# Pit_Crew.net
KiCad netlist of a schematic drawn in EAGLE
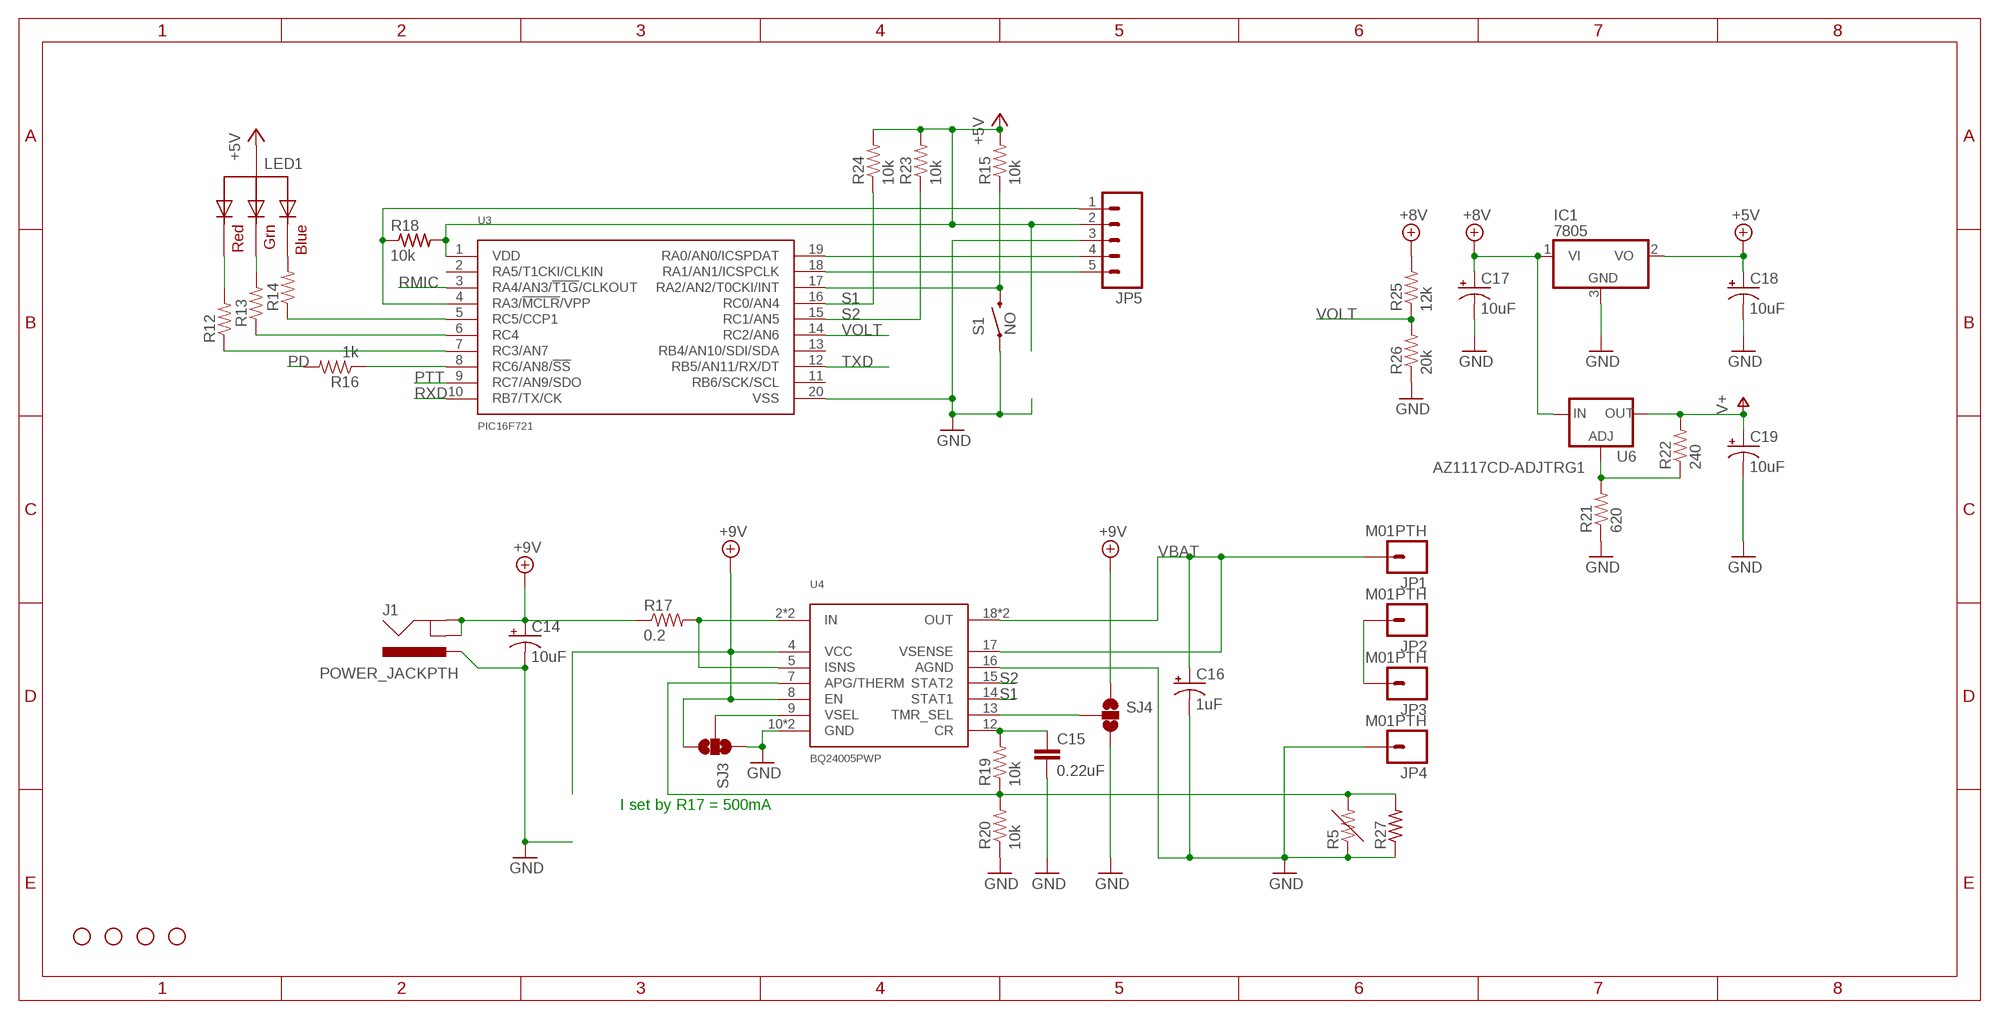
[diagram p0: schematic, sheet 1]
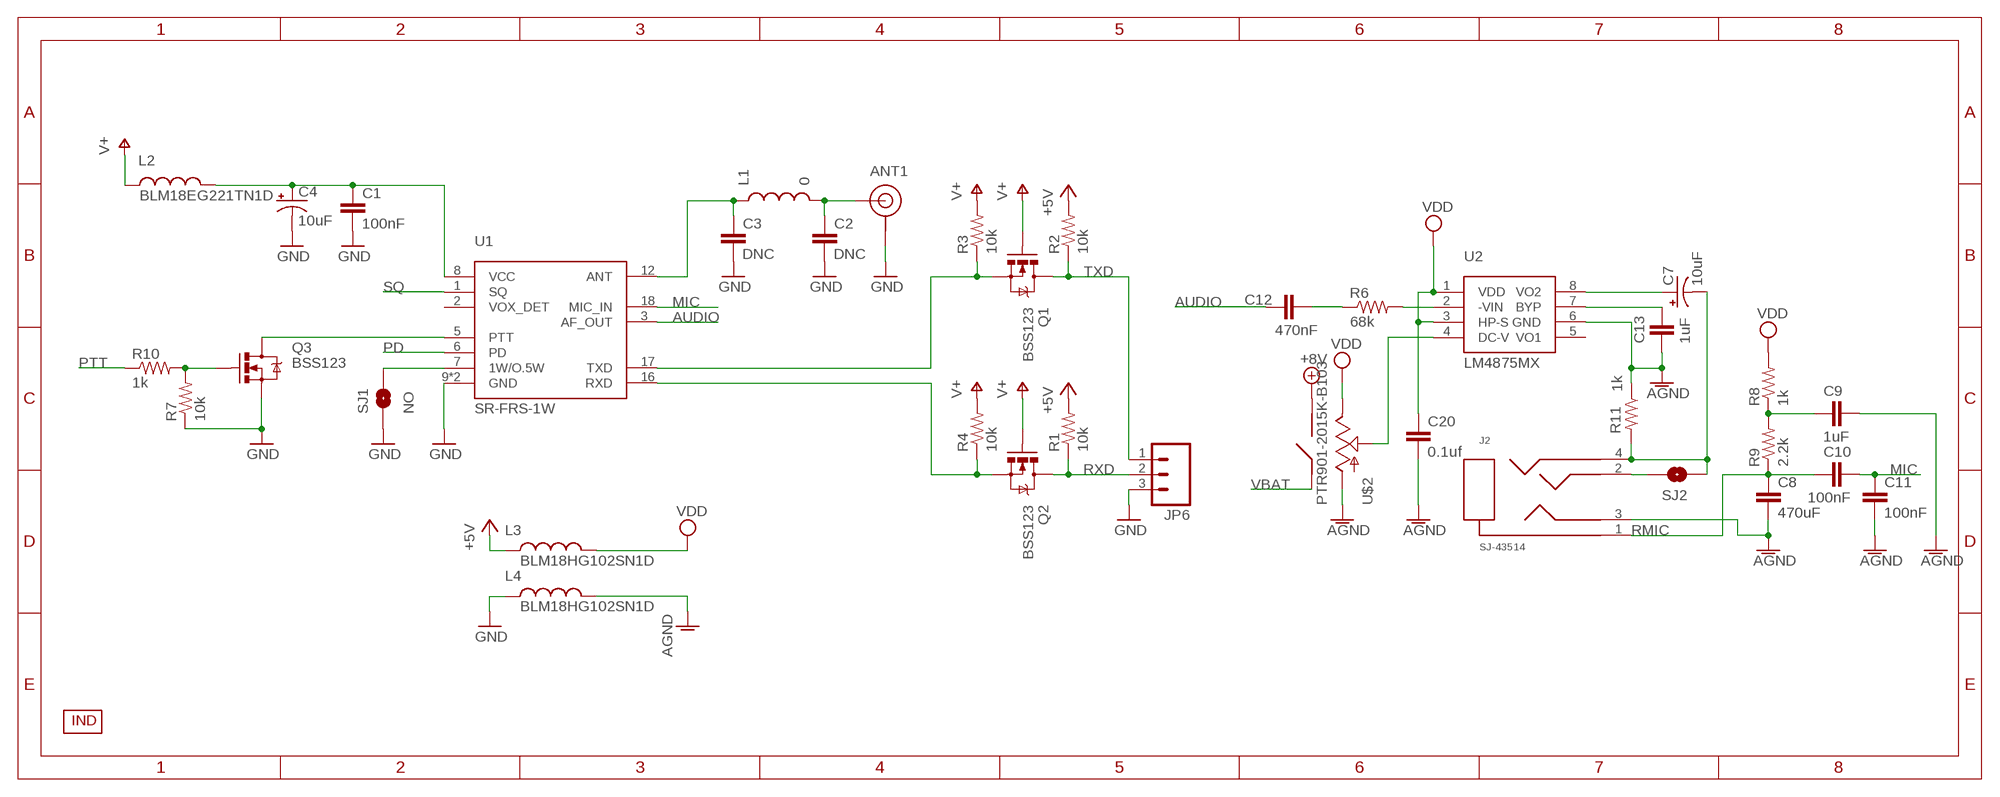
[diagram p1: schematic, sheet 2]

(export (version "E")
  (design (tool "Eeschema 10.0.6"))
  (components
    (comp (ref "ANT1")
      (value "SMA")
      (footprint "eagle-import:CONSMA002")
      (libsource (lib "eagle-import") (part "SMA"))
    )
    (comp (ref "C1")
      (value "100nF")
      (footprint "eagle-import:0805")
      (libsource (lib "eagle-import") (part "CAP0805"))
    )
    (comp (ref "C2")
      (value "DNC")
      (footprint "eagle-import:0805")
      (libsource (lib "eagle-import") (part "CAP0805"))
    )
    (comp (ref "C3")
      (value "DNC")
      (footprint "eagle-import:0805")
      (libsource (lib "eagle-import") (part "CAP0805"))
    )
    (comp (ref "C4")
      (value "10uF")
      (footprint "eagle-import:EIA3216")
      (libsource (lib "eagle-import") (part "CAP_POL1206"))
    )
    (comp (ref "C7")
      (value "10uF")
      (footprint "eagle-import:EIA3216")
      (libsource (lib "eagle-import") (part "10UF-TANT"))
    )
    (comp (ref "C8")
      (value "470uF")
      (footprint "eagle-import:0805")
      (libsource (lib "eagle-import") (part "CAP0805"))
    )
    (comp (ref "C9")
      (value "1uF")
      (footprint "eagle-import:0805")
      (libsource (lib "eagle-import") (part "CAP0805"))
    )
    (comp (ref "C10")
      (value "100nF")
      (footprint "eagle-import:0805")
      (libsource (lib "eagle-import") (part "CAP0805"))
    )
    (comp (ref "C11")
      (value "100nF")
      (footprint "eagle-import:0805")
      (libsource (lib "eagle-import") (part "CAP0805"))
    )
    (comp (ref "C12")
      (value "470nF")
      (footprint "eagle-import:0805")
      (libsource (lib "eagle-import") (part "CAP0805"))
    )
    (comp (ref "C13")
      (value "1uF")
      (footprint "eagle-import:0805")
      (libsource (lib "eagle-import") (part "CAP0805"))
    )
    (comp (ref "C20")
      (value "0.1uf")
      (footprint "eagle-import:0805")
      (libsource (lib "eagle-import") (part "CAP0805"))
    )
    (comp (ref "J2")
      (value "SJ-43514")
      (footprint "eagle-import:SJ-43514")
      (libsource (lib "eagle-import") (part "SJ-43514"))
    )
    (comp (ref "JP6")
      (value "M03LOCK")
      (footprint "eagle-import:1X03_LOCK")
      (libsource (lib "eagle-import") (part "M03LOCK"))
    )
    (comp (ref "L1")
      (value "0")
      (footprint "eagle-import:1007")
      (libsource (lib "eagle-import") (part "INDUCTOR1007"))
    )
    (comp (ref "L2")
      (value "BLM18EG221TN1D")
      (footprint "eagle-import:0603")
      (libsource (lib "eagle-import") (part "INDUCTOR0603"))
    )
    (comp (ref "L3")
      (value "BLM18HG102SN1D")
      (footprint "eagle-import:0603")
      (libsource (lib "eagle-import") (part "INDUCTOR0603"))
    )
    (comp (ref "L4")
      (value "BLM18HG102SN1D")
      (footprint "eagle-import:0603")
      (libsource (lib "eagle-import") (part "INDUCTOR0603"))
    )
    (comp (ref "Q1")
      (value "BSS123")
      (footprint "eagle-import:SOT23")
      (libsource (lib "eagle-import") (part "MOSFET-NCHANNELBSS123LT1G"))
    )
    (comp (ref "Q2")
      (value "BSS123")
      (footprint "eagle-import:SOT23")
      (libsource (lib "eagle-import") (part "MOSFET-NCHANNELBSS123LT1G"))
    )
    (comp (ref "Q3")
      (value "BSS123")
      (footprint "eagle-import:SOT23")
      (libsource (lib "eagle-import") (part "MOSFET-NCHANNELBSS123LT1G"))
    )
    (comp (ref "R1")
      (value "10k")
      (footprint "eagle-import:0805")
      (libsource (lib "eagle-import") (part "RESISTOR0805-RES"))
    )
    (comp (ref "R2")
      (value "10k")
      (footprint "eagle-import:0805")
      (libsource (lib "eagle-import") (part "RESISTOR0805-RES"))
    )
    (comp (ref "R3")
      (value "10k")
      (footprint "eagle-import:0805")
      (libsource (lib "eagle-import") (part "RESISTOR0805-RES"))
    )
    (comp (ref "R4")
      (value "10k")
      (footprint "eagle-import:0805")
      (libsource (lib "eagle-import") (part "RESISTOR0805-RES"))
    )
    (comp (ref "R6")
      (value "68k")
      (footprint "eagle-import:0805")
      (libsource (lib "eagle-import") (part "RESISTOR0805-RES"))
    )
    (comp (ref "R7")
      (value "10k")
      (footprint "eagle-import:0805")
      (libsource (lib "eagle-import") (part "RESISTOR0805-RES"))
    )
    (comp (ref "R8")
      (value "1k")
      (footprint "eagle-import:0805")
      (libsource (lib "eagle-import") (part "RESISTOR0805-RES"))
    )
    (comp (ref "R9")
      (value "2.2k")
      (footprint "eagle-import:0805")
      (libsource (lib "eagle-import") (part "RESISTOR0805-RES"))
    )
    (comp (ref "R10")
      (value "1k")
      (footprint "eagle-import:0805")
      (libsource (lib "eagle-import") (part "RESISTOR0805-RES"))
    )
    (comp (ref "R11")
      (value "1k")
      (footprint "eagle-import:0805")
      (libsource (lib "eagle-import") (part "RESISTOR0805-RES"))
    )
    (comp (ref "SJ1")
      (value "NO")
      (footprint "eagle-import:SJ_2S-NO")
      (libsource (lib "eagle-import") (part "SOLDERJUMPERNO"))
    )
    (comp (ref "SJ2")
      (value "SOLDERJUMPERNO")
      (footprint "eagle-import:SJ_2S-NO")
      (libsource (lib "eagle-import") (part "SOLDERJUMPERNO"))
    )
    (comp (ref "U$2")
      (value "PTR901-2015K-B103")
      (footprint "eagle-import:PTR901-2015K-B103")
      (libsource (lib "eagle-import") (part "PTR901-2015K-B103"))
    )
    (comp (ref "U$3")
      (value "INDPK1")
      (footprint "eagle-import:PICKIT-PIN-1")
      (libsource (lib "eagle-import") (part "INDPK1"))
    )
    (comp (ref "U1")
      (value "SR-FRS-1W")
      (footprint "eagle-import:SR-FRS-1W")
      (libsource (lib "eagle-import") (part "SR-FRS-1W"))
    )
    (comp (ref "U2")
      (value "LM4875MX")
      (footprint "eagle-import:SO-8")
      (libsource (lib "eagle-import") (part "LM4875MX"))
    )
    (comp (ref "C14")
      (value "10uF")
      (footprint "eagle-import:EIA3216")
      (libsource (lib "eagle-import") (part "10UF-TANT"))
    )
    (comp (ref "C15")
      (value "0.22uF")
      (footprint "eagle-import:0805")
      (libsource (lib "eagle-import") (part "CAP0805"))
    )
    (comp (ref "C16")
      (value "1uF")
      (footprint "eagle-import:EIA3216")
      (libsource (lib "eagle-import") (part "10UF-TANT"))
    )
    (comp (ref "C17")
      (value "10uF")
      (footprint "eagle-import:EIA3216")
      (libsource (lib "eagle-import") (part "10UF-TANT"))
    )
    (comp (ref "C18")
      (value "10uF")
      (footprint "eagle-import:EIA3216")
      (libsource (lib "eagle-import") (part "10UF-TANT"))
    )
    (comp (ref "C19")
      (value "10uF")
      (footprint "eagle-import:EIA3216")
      (libsource (lib "eagle-import") (part "10UF-TANT"))
    )
    (comp (ref "IC1")
      (value "7805")
      (footprint "eagle-import:TO252")
      (libsource (lib "eagle-import") (part "78DT06"))
    )
    (comp (ref "J1")
      (value "POWER_JACKPTH")
      (footprint "eagle-import:POWER_JACK_PTH")
      (libsource (lib "eagle-import") (part "POWER_JACKPTH"))
    )
    (comp (ref "JP1")
      (value "M01PTH")
      (footprint "eagle-import:1X01")
      (libsource (lib "eagle-import") (part "M01PTH"))
    )
    (comp (ref "JP2")
      (value "M01PTH")
      (footprint "eagle-import:1X01")
      (libsource (lib "eagle-import") (part "M01PTH"))
    )
    (comp (ref "JP3")
      (value "M01PTH")
      (footprint "eagle-import:1X01")
      (libsource (lib "eagle-import") (part "M01PTH"))
    )
    (comp (ref "JP4")
      (value "M01PTH")
      (footprint "eagle-import:1X01")
      (libsource (lib "eagle-import") (part "M01PTH"))
    )
    (comp (ref "JP5")
      (value "M05LOCK_LONGPADS")
      (footprint "eagle-import:1X05_LOCK_LONGPADS")
      (libsource (lib "eagle-import") (part "M05LOCK_LONGPADS"))
    )
    (comp (ref "LED1")
      (value "RGBLED_CA-5MM")
      (footprint "eagle-import:LED5MMRGB")
      (libsource (lib "eagle-import") (part "RGBLED_CA-5MM"))
    )
    (comp (ref "R5")
      (value "RESISTOR0805-RES")
      (footprint "eagle-import:0805")
      (libsource (lib "eagle-import") (part "RESISTOR0805-RES"))
    )
    (comp (ref "R12")
      (value "RESISTOR0805-RES")
      (footprint "eagle-import:0805")
      (libsource (lib "eagle-import") (part "RESISTOR0805-RES"))
    )
    (comp (ref "R13")
      (value "RESISTOR0805-RES")
      (footprint "eagle-import:0805")
      (libsource (lib "eagle-import") (part "RESISTOR0805-RES"))
    )
    (comp (ref "R14")
      (value "RESISTOR0805-RES")
      (footprint "eagle-import:0805")
      (libsource (lib "eagle-import") (part "RESISTOR0805-RES"))
    )
    (comp (ref "R15")
      (value "10k")
      (footprint "eagle-import:0805")
      (libsource (lib "eagle-import") (part "RESISTOR0805-RES"))
    )
    (comp (ref "R16")
      (value "1k")
      (footprint "eagle-import:0805")
      (libsource (lib "eagle-import") (part "RESISTOR0805-RES"))
    )
    (comp (ref "R17")
      (value "0.2")
      (footprint "eagle-import:R2512")
      (libsource (lib "eagle-import") (part "RESISTOR2512"))
    )
    (comp (ref "R18")
      (value "10k")
      (footprint "eagle-import:R0805")
      (libsource (lib "eagle-import") (part "R-US_R0805"))
    )
    (comp (ref "R19")
      (value "10k")
      (footprint "eagle-import:0805")
      (libsource (lib "eagle-import") (part "RESISTOR0805-RES"))
    )
    (comp (ref "R20")
      (value "10k")
      (footprint "eagle-import:0805")
      (libsource (lib "eagle-import") (part "RESISTOR0805-RES"))
    )
    (comp (ref "R21")
      (value "620")
      (footprint "eagle-import:0805")
      (libsource (lib "eagle-import") (part "RESISTOR0805-RES"))
    )
    (comp (ref "R22")
      (value "240")
      (footprint "eagle-import:0805")
      (libsource (lib "eagle-import") (part "RESISTOR0805-RES"))
    )
    (comp (ref "R23")
      (value "10k")
      (footprint "eagle-import:0805")
      (libsource (lib "eagle-import") (part "RESISTOR0805-RES"))
    )
    (comp (ref "R24")
      (value "10k")
      (footprint "eagle-import:0805")
      (libsource (lib "eagle-import") (part "RESISTOR0805-RES"))
    )
    (comp (ref "R25")
      (value "12k")
      (footprint "eagle-import:0805")
      (libsource (lib "eagle-import") (part "RESISTOR0805-RES"))
    )
    (comp (ref "R26")
      (value "20k")
      (footprint "eagle-import:0805")
      (libsource (lib "eagle-import") (part "RESISTOR0805-RES"))
    )
    (comp (ref "R27")
      (value "R-US_0207/7")
      (footprint "eagle-import:0207_7")
      (libsource (lib "eagle-import") (part "R-US_0207/7"))
    )
    (comp (ref "S1")
      (value "NO")
      (footprint "eagle-import:TACTILE-PTH-SIDEEZ")
      (libsource (lib "eagle-import") (part "SWITCH-MOMENTARY-2SIDE_EZ"))
    )
    (comp (ref "SJ3")
      (value "SOLDERJUMPER_2WAYS")
      (footprint "eagle-import:SJ_3")
      (libsource (lib "eagle-import") (part "SOLDERJUMPER_2WAYS"))
    )
    (comp (ref "SJ4")
      (value "SOLDERJUMPER_2WAYS")
      (footprint "eagle-import:SJ_3")
      (libsource (lib "eagle-import") (part "SOLDERJUMPER_2WAYS"))
    )
    (comp (ref "STANDOFF1")
      (value "STAND-OFF")
      (footprint "eagle-import:STAND-OFF")
      (libsource (lib "eagle-import") (part "STAND-OFF"))
    )
    (comp (ref "STANDOFF2")
      (value "STAND-OFF")
      (footprint "eagle-import:STAND-OFF")
      (libsource (lib "eagle-import") (part "STAND-OFF"))
    )
    (comp (ref "STANDOFF3")
      (value "STAND-OFF")
      (footprint "eagle-import:STAND-OFF")
      (libsource (lib "eagle-import") (part "STAND-OFF"))
    )
    (comp (ref "STANDOFF4")
      (value "STAND-OFF")
      (footprint "eagle-import:STAND-OFF")
      (libsource (lib "eagle-import") (part "STAND-OFF"))
    )
    (comp (ref "U3")
      (value "PIC16F721")
      (footprint "eagle-import:SSOP-20")
      (libsource (lib "eagle-import") (part "PIC16F721"))
    )
    (comp (ref "U4")
      (value "BQ24005PWP")
      (footprint "eagle-import:HTSSOP-20")
      (libsource (lib "eagle-import") (part "BQ24005PWP"))
    )
    (comp (ref "U6")
      (value "AZ1117CD-ADJTRG1")
      (footprint "eagle-import:V-REG_DPACK")
      (libsource (lib "eagle-import") (part "V_REG_317DPACK"))
    )
  )
  (nets
    (net (code "1") (name "+5V") (class "Default")
      (node (ref "C18") (pin "A") (pinfunction "+_A") (pintype "passive"))
      (node (ref "IC1") (pin "2") (pinfunction "VO_2") (pintype "passive"))
      (node (ref "JP5") (pin "2") (pinfunction "2_2") (pintype "passive"))
      (node (ref "L3") (pin "1") (pinfunction "1_1") (pintype "passive"))
      (node (ref "LED1") (pin "2") (pinfunction "VCC_2") (pintype "bidirectional"))
      (node (ref "R1") (pin "2") (pinfunction "2_2") (pintype "passive"))
      (node (ref "R15") (pin "2") (pinfunction "2_2") (pintype "passive"))
      (node (ref "R18") (pin "2") (pinfunction "2_2") (pintype "passive"))
      (node (ref "R2") (pin "2") (pinfunction "2_2") (pintype "passive"))
      (node (ref "R23") (pin "2") (pinfunction "2_2") (pintype "passive"))
      (node (ref "R24") (pin "2") (pinfunction "2_2") (pintype "passive"))
      (node (ref "U3") (pin "1") (pinfunction "VDD_1") (pintype "bidirectional"))
    )
    (net (code "2") (name "+8V") (class "Default")
      (node (ref "C17") (pin "A") (pinfunction "+_A") (pintype "passive"))
      (node (ref "IC1") (pin "1") (pinfunction "VI_1") (pintype "input"))
      (node (ref "R25") (pin "2") (pinfunction "2_2") (pintype "passive"))
      (node (ref "U$2") (pin "S1") (pinfunction "S1_S1") (pintype "passive"))
      (node (ref "U6") (pin "3") (pinfunction "IN_3") (pintype "input"))
    )
    (net (code "3") (name "+9V") (class "Default")
      (node (ref "C14") (pin "A") (pinfunction "+_A") (pintype "passive"))
      (node (ref "J1") (pin "GND") (pinfunction "GND_GND") (pintype "bidirectional"))
      (node (ref "J1") (pin "GNDBREAK") (pinfunction "GNDBREAK_GNDBREAK") (pintype "bidirectional"))
      (node (ref "R17") (pin "1") (pinfunction "1_1") (pintype "passive"))
      (node (ref "SJ3") (pin "3") (pinfunction "3_3") (pintype "passive"))
      (node (ref "SJ4") (pin "1") (pinfunction "1_1") (pintype "passive"))
      (node (ref "U4") (pin "4") (pinfunction "VCC_4") (pintype "bidirectional"))
      (node (ref "U4") (pin "8") (pinfunction "EN_8") (pintype "bidirectional"))
    )
    (net (code "4") (name "AGND") (class "Default")
      (node (ref "C11") (pin "2") (pinfunction "2_2") (pintype "passive"))
      (node (ref "C13") (pin "1") (pinfunction "1_1") (pintype "passive"))
      (node (ref "C20") (pin "2") (pinfunction "2_2") (pintype "passive"))
      (node (ref "C8") (pin "2") (pinfunction "2_2") (pintype "passive"))
      (node (ref "C9") (pin "2") (pinfunction "2_2") (pintype "passive"))
      (node (ref "J2") (pin "3") (pinfunction "3_3") (pintype "bidirectional"))
      (node (ref "L4") (pin "2") (pinfunction "2_2") (pintype "passive"))
      (node (ref "R11") (pin "1") (pinfunction "1_1") (pintype "passive"))
      (node (ref "U$2") (pin "1") (pinfunction "CCW_1") (pintype "passive"))
      (node (ref "U2") (pin "6") (pinfunction "GND_6") (pintype "bidirectional"))
    )
    (net (code "5") (name "AUDIO") (class "Default")
      (node (ref "C12") (pin "1") (pinfunction "1_1") (pintype "passive"))
      (node (ref "U1") (pin "3") (pinfunction "AF_OUT_3") (pintype "bidirectional"))
    )
    (net (code "6") (name "GND") (class "Default")
      (node (ref "ANT1") (pin "1") (pinfunction "GND_1") (pintype "bidirectional"))
      (node (ref "ANT1") (pin "2") (pinfunction "GND_2") (pintype "bidirectional"))
      (node (ref "ANT1") (pin "3") (pinfunction "GND_3") (pintype "bidirectional"))
      (node (ref "ANT1") (pin "4") (pinfunction "GND_4") (pintype "bidirectional"))
      (node (ref "C1") (pin "2") (pinfunction "2_2") (pintype "passive"))
      (node (ref "C14") (pin "C") (pinfunction "-_C") (pintype "passive"))
      (node (ref "C15") (pin "2") (pinfunction "2_2") (pintype "passive"))
      (node (ref "C16") (pin "C") (pinfunction "-_C") (pintype "passive"))
      (node (ref "C17") (pin "C") (pinfunction "-_C") (pintype "passive"))
      (node (ref "C18") (pin "C") (pinfunction "-_C") (pintype "passive"))
      (node (ref "C19") (pin "C") (pinfunction "-_C") (pintype "passive"))
      (node (ref "C2") (pin "2") (pinfunction "2_2") (pintype "passive"))
      (node (ref "C3") (pin "2") (pinfunction "2_2") (pintype "passive"))
      (node (ref "C4") (pin "C") (pinfunction "-_C") (pintype "passive"))
      (node (ref "IC1") (pin "3") (pinfunction "GND_3") (pintype "passive"))
      (node (ref "J1") (pin "PWR") (pinfunction "PWR_PWR") (pintype "bidirectional"))
      (node (ref "JP4") (pin "1") (pinfunction "1_1") (pintype "passive"))
      (node (ref "JP5") (pin "3") (pinfunction "3_3") (pintype "passive"))
      (node (ref "JP6") (pin "3") (pinfunction "3_3") (pintype "passive"))
      (node (ref "L4") (pin "1") (pinfunction "1_1") (pintype "passive"))
      (node (ref "Q3") (pin "2") (pinfunction "S_2") (pintype "passive"))
      (node (ref "R20") (pin "1") (pinfunction "1_1") (pintype "passive"))
      (node (ref "R21") (pin "1") (pinfunction "1_1") (pintype "passive"))
      (node (ref "R26") (pin "1") (pinfunction "1_1") (pintype "passive"))
      (node (ref "R27") (pin "1") (pinfunction "1_1") (pintype "passive"))
      (node (ref "R5") (pin "1") (pinfunction "1_1") (pintype "passive"))
      (node (ref "R7") (pin "1") (pinfunction "1_1") (pintype "passive"))
      (node (ref "S1") (pin "1") (pinfunction "1_1") (pintype "passive"))
      (node (ref "SJ1") (pin "1") (pinfunction "1_1") (pintype "passive"))
      (node (ref "SJ3") (pin "1") (pinfunction "1_1") (pintype "passive"))
      (node (ref "SJ4") (pin "3") (pinfunction "3_3") (pintype "passive"))
      (node (ref "U1") (pin "10") (pinfunction "GND_10") (pintype "bidirectional"))
      (node (ref "U1") (pin "9") (pinfunction "GND_9") (pintype "bidirectional"))
      (node (ref "U3") (pin "20") (pinfunction "VSS_20") (pintype "bidirectional"))
      (node (ref "U4") (pin "10") (pinfunction "GND_10") (pintype "bidirectional"))
      (node (ref "U4") (pin "16") (pinfunction "AGND_16") (pintype "bidirectional"))
      (node (ref "U4") (pin "EP") (pinfunction "GND_EP") (pintype "bidirectional"))
    )
    (net (code "7") (name "MIC") (class "Default")
      (node (ref "C10") (pin "2") (pinfunction "2_2") (pintype "passive"))
      (node (ref "C11") (pin "1") (pinfunction "1_1") (pintype "passive"))
      (node (ref "U1") (pin "18") (pinfunction "MIC_IN_18") (pintype "bidirectional"))
    )
    (net (code "8") (name "Net-(ANT1-SIGNAL)") (class "Default")
      (node (ref "ANT1") (pin "C") (pinfunction "SIGNAL_C") (pintype "bidirectional"))
      (node (ref "C2") (pin "1") (pinfunction "1_1") (pintype "passive"))
      (node (ref "L1") (pin "2") (pinfunction "2_2") (pintype "passive"))
    )
    (net (code "9") (name "Net-(C4-+)") (class "Default")
      (node (ref "C1") (pin "1") (pinfunction "1_1") (pintype "passive"))
      (node (ref "C4") (pin "A") (pinfunction "+_A") (pintype "passive"))
      (node (ref "L2") (pin "2") (pinfunction "2_2") (pintype "passive"))
      (node (ref "U1") (pin "8") (pinfunction "VCC_8") (pintype "bidirectional"))
    )
    (net (code "10") (name "Net-(C7-+)") (class "Default")
      (node (ref "C7") (pin "A") (pinfunction "+_A") (pintype "passive"))
      (node (ref "U2") (pin "8") (pinfunction "VO2_8") (pintype "bidirectional"))
    )
    (net (code "11") (name "Net-(C7--)") (class "Default")
      (node (ref "C7") (pin "C") (pinfunction "-_C") (pintype "passive"))
      (node (ref "J2") (pin "4") (pinfunction "4_4") (pintype "bidirectional"))
      (node (ref "R11") (pin "2") (pinfunction "2_2") (pintype "passive"))
      (node (ref "SJ2") (pin "2") (pinfunction "2_2") (pintype "passive"))
    )
    (net (code "12") (name "Net-(C9-Pad1)") (class "Default")
      (node (ref "C9") (pin "1") (pinfunction "1_1") (pintype "passive"))
      (node (ref "R8") (pin "1") (pinfunction "1_1") (pintype "passive"))
      (node (ref "R9") (pin "2") (pinfunction "2_2") (pintype "passive"))
    )
    (net (code "13") (name "Net-(C12-Pad2)") (class "Default")
      (node (ref "C12") (pin "2") (pinfunction "2_2") (pintype "passive"))
      (node (ref "R6") (pin "1") (pinfunction "1_1") (pintype "passive"))
    )
    (net (code "14") (name "Net-(J2-Pad2)") (class "Default")
      (node (ref "J2") (pin "2") (pinfunction "2_2") (pintype "bidirectional"))
      (node (ref "SJ2") (pin "1") (pinfunction "1_1") (pintype "passive"))
    )
    (net (code "15") (name "Net-(JP2-Pad1)") (class "Default")
      (node (ref "JP2") (pin "1") (pinfunction "1_1") (pintype "passive"))
      (node (ref "JP3") (pin "1") (pinfunction "1_1") (pintype "passive"))
    )
    (net (code "16") (name "Net-(LED1-BLUE)") (class "Default")
      (node (ref "LED1") (pin "4") (pinfunction "BLUE_4") (pintype "bidirectional"))
      (node (ref "R14") (pin "2") (pinfunction "2_2") (pintype "passive"))
    )
    (net (code "17") (name "Net-(LED1-GREEN)") (class "Default")
      (node (ref "LED1") (pin "3") (pinfunction "GREEN_3") (pintype "bidirectional"))
      (node (ref "R13") (pin "2") (pinfunction "2_2") (pintype "passive"))
    )
    (net (code "18") (name "Net-(LED1-RED)") (class "Default")
      (node (ref "LED1") (pin "1") (pinfunction "RED_1") (pintype "bidirectional"))
      (node (ref "R12") (pin "2") (pinfunction "2_2") (pintype "passive"))
    )
    (net (code "19") (name "Net-(Q1-S)") (class "Default")
      (node (ref "Q1") (pin "2") (pinfunction "S_2") (pintype "passive"))
      (node (ref "R3") (pin "1") (pinfunction "1_1") (pintype "passive"))
      (node (ref "U1") (pin "17") (pinfunction "TXD_17") (pintype "bidirectional"))
    )
    (net (code "20") (name "Net-(Q2-S)") (class "Default")
      (node (ref "Q2") (pin "2") (pinfunction "S_2") (pintype "passive"))
      (node (ref "R4") (pin "1") (pinfunction "1_1") (pintype "passive"))
      (node (ref "U1") (pin "16") (pinfunction "RXD_16") (pintype "bidirectional"))
    )
    (net (code "21") (name "Net-(Q3-D)") (class "Default")
      (node (ref "Q3") (pin "3") (pinfunction "D_3") (pintype "passive"))
      (node (ref "U1") (pin "5") (pinfunction "PTT_5") (pintype "bidirectional"))
    )
    (net (code "22") (name "Net-(Q3-G)") (class "Default")
      (node (ref "Q3") (pin "1") (pinfunction "G_1") (pintype "passive"))
      (node (ref "R10") (pin "2") (pinfunction "2_2") (pintype "passive"))
      (node (ref "R7") (pin "2") (pinfunction "2_2") (pintype "passive"))
    )
    (net (code "23") (name "Net-(U$2-W)") (class "Default")
      (node (ref "U$2") (pin "2") (pinfunction "W_2") (pintype "passive"))
      (node (ref "U2") (pin "4") (pinfunction "DC-V_4") (pintype "bidirectional"))
    )
    (net (code "24") (name "Net-(U1-1W{slash}O.5W)") (class "Default")
      (node (ref "SJ1") (pin "2") (pinfunction "2_2") (pintype "passive"))
      (node (ref "U1") (pin "7") (pinfunction "1W/O.5W_7") (pintype "bidirectional"))
    )
    (net (code "25") (name "Net-(U1-ANT)") (class "Default")
      (node (ref "C3") (pin "1") (pinfunction "1_1") (pintype "passive"))
      (node (ref "L1") (pin "1") (pinfunction "1_1") (pintype "passive"))
      (node (ref "U1") (pin "12") (pinfunction "ANT_12") (pintype "bidirectional"))
    )
    (net (code "26") (name "Net-(U2--VIN)") (class "Default")
      (node (ref "R6") (pin "2") (pinfunction "2_2") (pintype "passive"))
      (node (ref "U2") (pin "2") (pinfunction "-VIN_2") (pintype "bidirectional"))
    )
    (net (code "27") (name "Net-(U2-BYP)") (class "Default")
      (node (ref "C13") (pin "2") (pinfunction "2_2") (pintype "passive"))
      (node (ref "U2") (pin "7") (pinfunction "BYP_7") (pintype "bidirectional"))
    )
    (net (code "28") (name "Net-(U3-RA0{slash}AN0{slash}ICSPDAT)") (class "Default")
      (node (ref "JP5") (pin "4") (pinfunction "4_4") (pintype "passive"))
      (node (ref "U3") (pin "19") (pinfunction "RA0/AN0/ICSPDAT_19") (pintype "bidirectional"))
    )
    (net (code "29") (name "Net-(U3-RA1{slash}AN1{slash}ICSPCLK)") (class "Default")
      (node (ref "JP5") (pin "5") (pinfunction "5_5") (pintype "passive"))
      (node (ref "U3") (pin "18") (pinfunction "RA1/AN1/ICSPCLK_18") (pintype "bidirectional"))
    )
    (net (code "30") (name "Net-(U3-RA2{slash}AN2{slash}T0CKI{slash}INT)") (class "Default")
      (node (ref "R15") (pin "1") (pinfunction "1_1") (pintype "passive"))
      (node (ref "S1") (pin "2") (pinfunction "2_2") (pintype "passive"))
      (node (ref "U3") (pin "17") (pinfunction "RA2/AN2/T0CKI/INT_17") (pintype "bidirectional"))
    )
    (net (code "31") (name "Net-(U3-RA3{slash}~{MCLR}{slash}VPP)") (class "Default")
      (node (ref "JP5") (pin "1") (pinfunction "1_1") (pintype "passive"))
      (node (ref "R18") (pin "1") (pinfunction "1_1") (pintype "passive"))
      (node (ref "U3") (pin "4") (pinfunction "RA3/~{MCLR}/VPP_4") (pintype "bidirectional"))
    )
    (net (code "32") (name "Net-(U3-RC3{slash}AN7)") (class "Default")
      (node (ref "R12") (pin "1") (pinfunction "1_1") (pintype "passive"))
      (node (ref "U3") (pin "7") (pinfunction "RC3/AN7_7") (pintype "bidirectional"))
    )
    (net (code "33") (name "Net-(U3-RC4)") (class "Default")
      (node (ref "R13") (pin "1") (pinfunction "1_1") (pintype "passive"))
      (node (ref "U3") (pin "6") (pinfunction "RC4_6") (pintype "bidirectional"))
    )
    (net (code "34") (name "Net-(U3-RC5{slash}CCP1)") (class "Default")
      (node (ref "R14") (pin "1") (pinfunction "1_1") (pintype "passive"))
      (node (ref "U3") (pin "5") (pinfunction "RC5/CCP1_5") (pintype "bidirectional"))
    )
    (net (code "35") (name "Net-(U3-RC6{slash}AN8{slash}~{SS})") (class "Default")
      (node (ref "R16") (pin "1") (pinfunction "1_1") (pintype "passive"))
      (node (ref "U3") (pin "8") (pinfunction "RC6/AN8/~{SS}_8") (pintype "bidirectional"))
    )
    (net (code "36") (name "Net-(U4-APG{slash}THERM)") (class "Default")
      (node (ref "R19") (pin "1") (pinfunction "1_1") (pintype "passive"))
      (node (ref "R20") (pin "2") (pinfunction "2_2") (pintype "passive"))
      (node (ref "R27") (pin "2") (pinfunction "2_2") (pintype "passive"))
      (node (ref "R5") (pin "2") (pinfunction "2_2") (pintype "passive"))
      (node (ref "U4") (pin "7") (pinfunction "APG/THERM_7") (pintype "bidirectional"))
    )
    (net (code "37") (name "Net-(U4-CR)") (class "Default")
      (node (ref "C15") (pin "1") (pinfunction "1_1") (pintype "passive"))
      (node (ref "R19") (pin "2") (pinfunction "2_2") (pintype "passive"))
      (node (ref "U4") (pin "12") (pinfunction "CR_12") (pintype "bidirectional"))
    )
    (net (code "38") (name "Net-(U4-ISNS)") (class "Default")
      (node (ref "R17") (pin "2") (pinfunction "2_2") (pintype "passive"))
      (node (ref "U4") (pin "2") (pinfunction "IN_2") (pintype "bidirectional"))
      (node (ref "U4") (pin "3") (pinfunction "IN_3") (pintype "bidirectional"))
      (node (ref "U4") (pin "5") (pinfunction "ISNS_5") (pintype "bidirectional"))
    )
    (net (code "39") (name "Net-(U4-TMR_SEL)") (class "Default")
      (node (ref "SJ4") (pin "2") (pinfunction "2_2") (pintype "passive"))
      (node (ref "U4") (pin "13") (pinfunction "TMR_SEL_13") (pintype "bidirectional"))
    )
    (net (code "40") (name "Net-(U4-VSEL)") (class "Default")
      (node (ref "SJ3") (pin "2") (pinfunction "2_2") (pintype "passive"))
      (node (ref "U4") (pin "9") (pinfunction "VSEL_9") (pintype "bidirectional"))
    )
    (net (code "41") (name "Net-(U6-ADJ)") (class "Default")
      (node (ref "R21") (pin "2") (pinfunction "2_2") (pintype "passive"))
      (node (ref "R22") (pin "1") (pinfunction "1_1") (pintype "passive"))
      (node (ref "U6") (pin "1") (pinfunction "ADJ_1") (pintype "input"))
    )
    (net (code "42") (name "PD") (class "Default")
      (node (ref "R16") (pin "2") (pinfunction "2_2") (pintype "passive"))
      (node (ref "U1") (pin "6") (pinfunction "PD_6") (pintype "bidirectional"))
    )
    (net (code "43") (name "PTT") (class "Default")
      (node (ref "R10") (pin "1") (pinfunction "1_1") (pintype "passive"))
      (node (ref "U3") (pin "9") (pinfunction "RC7/AN9/SDO_9") (pintype "bidirectional"))
    )
    (net (code "44") (name "RMIC") (class "Default")
      (node (ref "C10") (pin "1") (pinfunction "1_1") (pintype "passive"))
      (node (ref "C8") (pin "1") (pinfunction "1_1") (pintype "passive"))
      (node (ref "J2") (pin "1") (pinfunction "1_1") (pintype "bidirectional"))
      (node (ref "R9") (pin "1") (pinfunction "1_1") (pintype "passive"))
      (node (ref "U3") (pin "3") (pinfunction "RA4/AN3/~{T1G}/CLKOUT_3") (pintype "bidirectional"))
    )
    (net (code "45") (name "RXD") (class "Default")
      (node (ref "JP6") (pin "2") (pinfunction "2_2") (pintype "passive"))
      (node (ref "Q2") (pin "3") (pinfunction "D_3") (pintype "passive"))
      (node (ref "R1") (pin "1") (pinfunction "1_1") (pintype "passive"))
      (node (ref "U3") (pin "10") (pinfunction "RB7/TX/CK_10") (pintype "bidirectional"))
    )
    (net (code "46") (name "S1") (class "Default")
      (node (ref "R24") (pin "1") (pinfunction "1_1") (pintype "passive"))
      (node (ref "U3") (pin "16") (pinfunction "RC0/AN4_16") (pintype "bidirectional"))
      (node (ref "U4") (pin "14") (pinfunction "STAT1_14") (pintype "bidirectional"))
    )
    (net (code "47") (name "S2") (class "Default")
      (node (ref "R23") (pin "1") (pinfunction "1_1") (pintype "passive"))
      (node (ref "U3") (pin "15") (pinfunction "RC1/AN5_15") (pintype "bidirectional"))
      (node (ref "U4") (pin "15") (pinfunction "STAT2_15") (pintype "bidirectional"))
    )
    (net (code "48") (name "SQ") (class "Default")
      (node (ref "U1") (pin "1") (pinfunction "SQ_1") (pintype "bidirectional"))
    )
    (net (code "49") (name "TXD") (class "Default")
      (node (ref "JP6") (pin "1") (pinfunction "1_1") (pintype "passive"))
      (node (ref "Q1") (pin "3") (pinfunction "D_3") (pintype "passive"))
      (node (ref "R2") (pin "1") (pinfunction "1_1") (pintype "passive"))
      (node (ref "U3") (pin "12") (pinfunction "RB5/AN11/RX/DT_12") (pintype "bidirectional"))
    )
    (net (code "50") (name "V+") (class "Default")
      (node (ref "C19") (pin "A") (pinfunction "+_A") (pintype "passive"))
      (node (ref "L2") (pin "1") (pinfunction "1_1") (pintype "passive"))
      (node (ref "Q1") (pin "1") (pinfunction "G_1") (pintype "passive"))
      (node (ref "Q2") (pin "1") (pinfunction "G_1") (pintype "passive"))
      (node (ref "R22") (pin "2") (pinfunction "2_2") (pintype "passive"))
      (node (ref "R3") (pin "2") (pinfunction "2_2") (pintype "passive"))
      (node (ref "R4") (pin "2") (pinfunction "2_2") (pintype "passive"))
      (node (ref "U6") (pin "4") (pinfunction "OUT_4") (pintype "output"))
    )
    (net (code "51") (name "VBAT") (class "Default")
      (node (ref "C16") (pin "A") (pinfunction "+_A") (pintype "passive"))
      (node (ref "JP1") (pin "1") (pinfunction "1_1") (pintype "passive"))
      (node (ref "U$2") (pin "S2") (pinfunction "S2_S2") (pintype "passive"))
      (node (ref "U4") (pin "17") (pinfunction "VSENSE_17") (pintype "bidirectional"))
      (node (ref "U4") (pin "18") (pinfunction "OUT_18") (pintype "bidirectional"))
      (node (ref "U4") (pin "19") (pinfunction "OUT_19") (pintype "bidirectional"))
    )
    (net (code "52") (name "VDD") (class "Default")
      (node (ref "C20") (pin "1") (pinfunction "1_1") (pintype "passive"))
      (node (ref "L3") (pin "2") (pinfunction "2_2") (pintype "passive"))
      (node (ref "R8") (pin "2") (pinfunction "2_2") (pintype "passive"))
      (node (ref "U$2") (pin "3") (pinfunction "CW_3") (pintype "passive"))
      (node (ref "U2") (pin "1") (pinfunction "VDD_1") (pintype "bidirectional"))
      (node (ref "U2") (pin "3") (pinfunction "HP-S_3") (pintype "bidirectional"))
    )
    (net (code "53") (name "VOLT") (class "Default")
      (node (ref "R25") (pin "1") (pinfunction "1_1") (pintype "passive"))
      (node (ref "R26") (pin "2") (pinfunction "2_2") (pintype "passive"))
      (node (ref "U3") (pin "14") (pinfunction "RC2/AN6_14") (pintype "bidirectional"))
    )
    (net (code "54") (name "unconnected-(U1-VOX_DET-Pad2)") (class "Default")
      (node (ref "U1") (pin "2") (pinfunction "VOX_DET_2") (pintype "bidirectional"))
    )
    (net (code "55") (name "unconnected-(U2-VO1-Pad5)") (class "Default")
      (node (ref "U2") (pin "5") (pinfunction "VO1_5") (pintype "bidirectional"))
    )
    (net (code "56") (name "unconnected-(U3-RA5{slash}T1CKI{slash}CLKIN-Pad2)") (class "Default")
      (node (ref "U3") (pin "2") (pinfunction "RA5/T1CKI/CLKIN_2") (pintype "bidirectional"))
    )
    (net (code "57") (name "unconnected-(U3-RB4{slash}AN10{slash}SDI{slash}SDA-Pad13)") (class "Default")
      (node (ref "U3") (pin "13") (pinfunction "RB4/AN10/SDI/SDA_13") (pintype "bidirectional"))
    )
    (net (code "58") (name "unconnected-(U3-RB6{slash}SCK{slash}SCL-Pad11)") (class "Default")
      (node (ref "U3") (pin "11") (pinfunction "RB6/SCK/SCL_11") (pintype "bidirectional"))
    )
  )
)
